# Cubesat.net
KiCad netlist of a schematic drawn in EAGLE
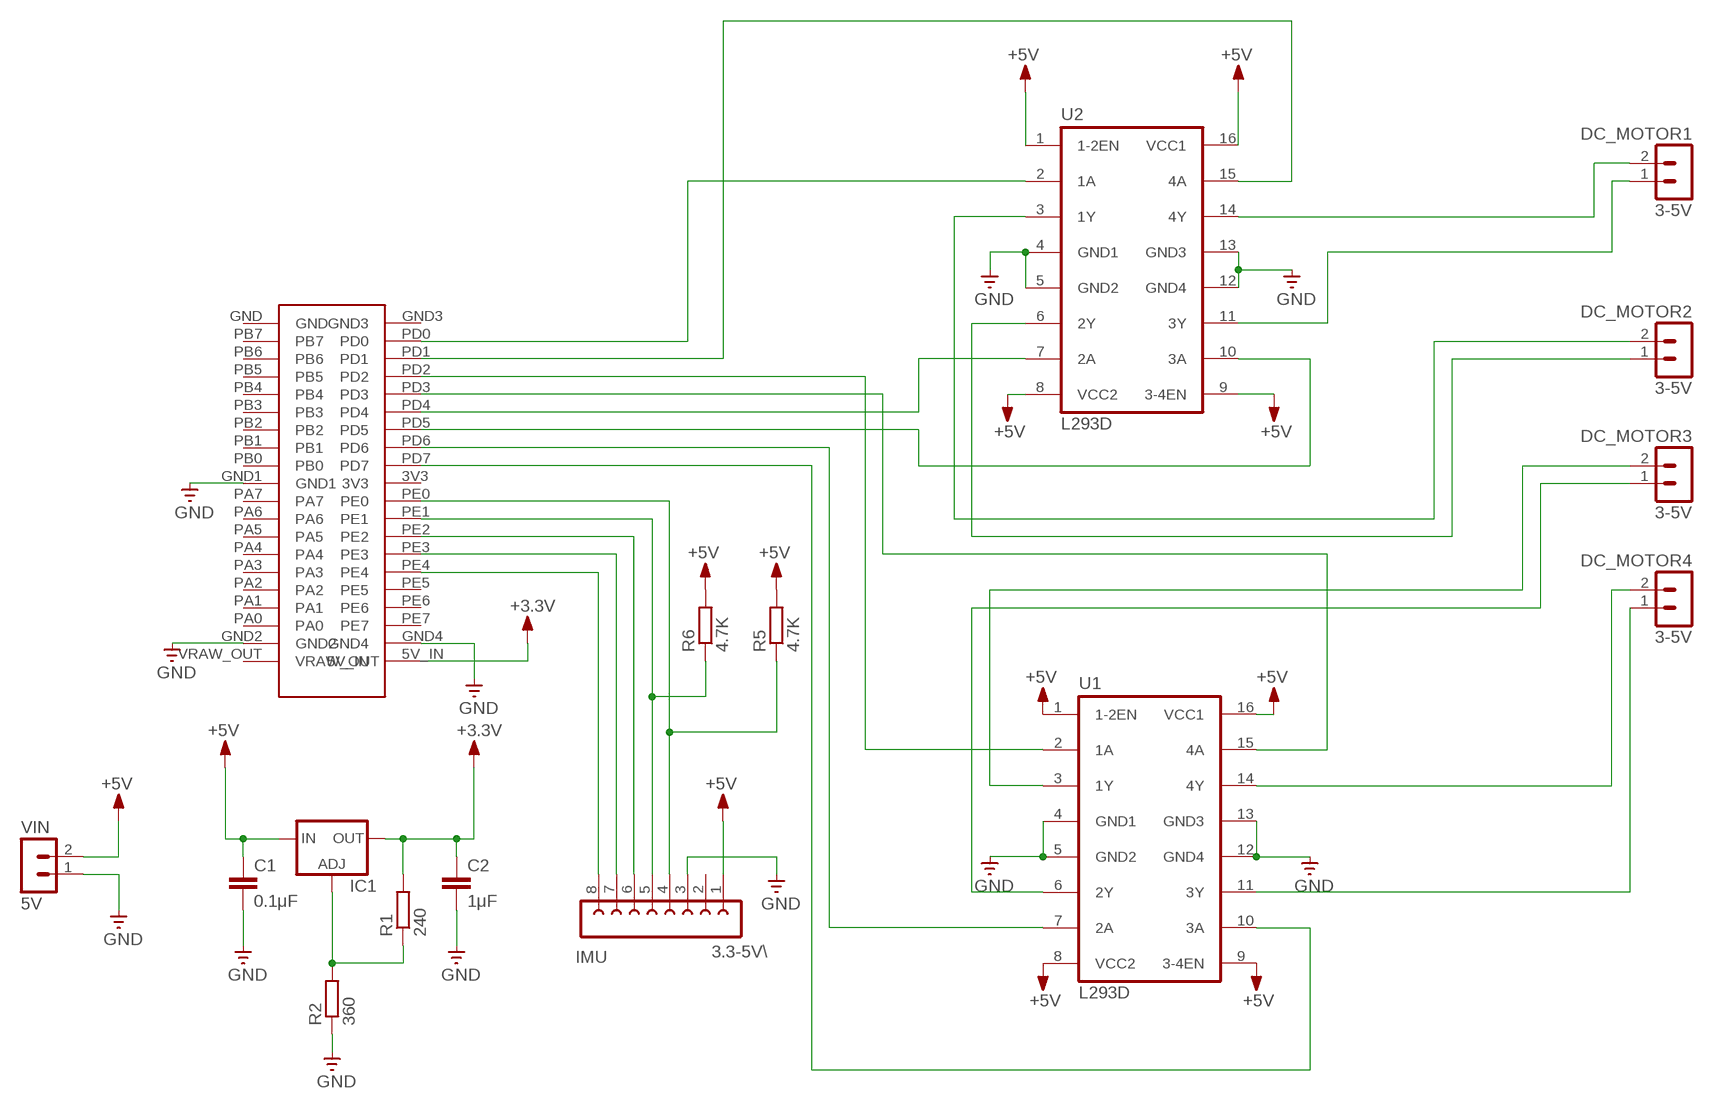
[diagram p0: schematic, sheet 1]

(export (version "E")
  (design (tool "Eeschema 10.0.6"))
  (components
    (comp (ref "C1")
      (value "0.1μF")
      (footprint "eagle-import:C1210")
      (libsource (lib "eagle-import") (part "C-EUC1210"))
    )
    (comp (ref "C2")
      (value "1μF")
      (footprint "eagle-import:C1210")
      (libsource (lib "eagle-import") (part "C-EUC1210"))
    )
    (comp (ref "DC_MOTOR1")
      (value "3-5V")
      (footprint "eagle-import:MA02-1Y")
      (libsource (lib "eagle-import") (part "MA02-1Y"))
    )
    (comp (ref "DC_MOTOR2")
      (value "3-5V")
      (footprint "eagle-import:MA02-1Y")
      (libsource (lib "eagle-import") (part "MA02-1Y"))
    )
    (comp (ref "DC_MOTOR3")
      (value "3-5V")
      (footprint "eagle-import:MA02-1Y")
      (libsource (lib "eagle-import") (part "MA02-1Y"))
    )
    (comp (ref "DC_MOTOR4")
      (value "3-5V")
      (footprint "eagle-import:MA02-1Y")
      (libsource (lib "eagle-import") (part "MA02-1Y"))
    )
    (comp (ref "IC1")
      (value "LM317TS")
      (footprint "eagle-import:317TS")
      (libsource (lib "eagle-import") (part "LM317TS"))
    )
    (comp (ref "IMU")
      (value "3.3-5V\\")
      (footprint "eagle-import:FE08-1")
      (libsource (lib "eagle-import") (part "FE08-1"))
    )
    (comp (ref "R1")
      (value "240")
      (footprint "eagle-import:M2012")
      (libsource (lib "eagle-import") (part "R-EU_M2012"))
    )
    (comp (ref "R2")
      (value "360")
      (footprint "eagle-import:M2012")
      (libsource (lib "eagle-import") (part "R-EU_M2012"))
    )
    (comp (ref "R5")
      (value "4.7K")
      (footprint "eagle-import:M2012")
      (libsource (lib "eagle-import") (part "R-EU_M2012"))
    )
    (comp (ref "R6")
      (value "4.7K")
      (footprint "eagle-import:M2012")
      (libsource (lib "eagle-import") (part "R-EU_M2012"))
    )
    (comp (ref "U1")
      (value "L293D")
      (footprint "eagle-import:DIL16")
      (libsource (lib "eagle-import") (part "L293D"))
    )
    (comp (ref "U2")
      (value "L293D")
      (footprint "eagle-import:DIL16")
      (libsource (lib "eagle-import") (part "L293D"))
    )
    (comp (ref "VIN")
      (value "5V")
      (footprint "eagle-import:MA02-1Y")
      (libsource (lib "eagle-import") (part "MA02-1Y"))
    )
    (comp (ref "XMEGA256A3U")
      (value "ATXMEGA256A3U")
      (footprint "eagle-import:ATXMEGA256A3U")
      (libsource (lib "eagle-import") (part "ATXMEGA256A3U"))
    )
  )
  (nets
    (net (code "1") (name "+3.3V") (class "Default")
      (node (ref "C1") (pin "1") (pinfunction "1_1") (pintype "passive"))
      (node (ref "C2") (pin "1") (pinfunction "1_1") (pintype "passive"))
      (node (ref "IC1") (pin "2") (pinfunction "OUT_2") (pintype "passive"))
      (node (ref "IC1") (pin "3") (pinfunction "IN_3") (pintype "input"))
      (node (ref "IMU") (pin "1") (pinfunction "1_1") (pintype "passive"))
      (node (ref "R1") (pin "2") (pinfunction "2_2") (pintype "passive"))
      (node (ref "R5") (pin "2") (pinfunction "2_2") (pintype "passive"))
      (node (ref "R6") (pin "2") (pinfunction "2_2") (pintype "passive"))
      (node (ref "U1") (pin "1") (pinfunction "1-2EN_1") (pintype "input"))
      (node (ref "U1") (pin "16") (pinfunction "VCC1_16") (pintype "power_in"))
      (node (ref "U1") (pin "8") (pinfunction "VCC2_8") (pintype "power_in"))
      (node (ref "U1") (pin "9") (pinfunction "3-4EN_9") (pintype "input"))
      (node (ref "U2") (pin "1") (pinfunction "1-2EN_1") (pintype "input"))
      (node (ref "U2") (pin "16") (pinfunction "VCC1_16") (pintype "power_in"))
      (node (ref "U2") (pin "8") (pinfunction "VCC2_8") (pintype "power_in"))
      (node (ref "U2") (pin "9") (pinfunction "3-4EN_9") (pintype "input"))
      (node (ref "VIN") (pin "2") (pinfunction "2_2") (pintype "passive"))
      (node (ref "XMEGA256A3U") (pin "5V_IN") (pinfunction "5V_IN_5V_IN") (pintype "bidirectional"))
    )
    (net (code "2") (name "GND") (class "Default")
      (node (ref "C1") (pin "2") (pinfunction "2_2") (pintype "passive"))
      (node (ref "C2") (pin "2") (pinfunction "2_2") (pintype "passive"))
      (node (ref "IMU") (pin "3") (pinfunction "3_3") (pintype "passive"))
      (node (ref "R2") (pin "1") (pinfunction "1_1") (pintype "passive"))
      (node (ref "U1") (pin "12") (pinfunction "GND4_12") (pintype "power_in"))
      (node (ref "U1") (pin "13") (pinfunction "GND3_13") (pintype "power_in"))
      (node (ref "U1") (pin "4") (pinfunction "GND1_4") (pintype "power_in"))
      (node (ref "U1") (pin "5") (pinfunction "GND2_5") (pintype "power_in"))
      (node (ref "U2") (pin "12") (pinfunction "GND4_12") (pintype "power_in"))
      (node (ref "U2") (pin "13") (pinfunction "GND3_13") (pintype "power_in"))
      (node (ref "U2") (pin "4") (pinfunction "GND1_4") (pintype "power_in"))
      (node (ref "U2") (pin "5") (pinfunction "GND2_5") (pintype "power_in"))
      (node (ref "VIN") (pin "1") (pinfunction "1_1") (pintype "passive"))
      (node (ref "XMEGA256A3U") (pin "GND1") (pinfunction "GND1_GND1") (pintype "bidirectional"))
      (node (ref "XMEGA256A3U") (pin "GND2") (pinfunction "GND2_GND2") (pintype "bidirectional"))
      (node (ref "XMEGA256A3U") (pin "GND4") (pinfunction "GND4_GND4") (pintype "bidirectional"))
    )
    (net (code "3") (name "Net-(IC1-ADJ)") (class "Default")
      (node (ref "IC1") (pin "1") (pinfunction "ADJ_1") (pintype "input"))
      (node (ref "R1") (pin "1") (pinfunction "1_1") (pintype "passive"))
      (node (ref "R2") (pin "2") (pinfunction "2_2") (pintype "passive"))
    )
    (net (code "4") (name "Net-(IMU-Pad4)") (class "Default")
      (node (ref "IMU") (pin "4") (pinfunction "4_4") (pintype "passive"))
      (node (ref "R5") (pin "1") (pinfunction "1_1") (pintype "passive"))
      (node (ref "XMEGA256A3U") (pin "PE0") (pinfunction "PE0_PE0") (pintype "bidirectional"))
    )
    (net (code "5") (name "Net-(IMU-Pad5)") (class "Default")
      (node (ref "IMU") (pin "5") (pinfunction "5_5") (pintype "passive"))
      (node (ref "R6") (pin "1") (pinfunction "1_1") (pintype "passive"))
      (node (ref "XMEGA256A3U") (pin "PE1") (pinfunction "PE1_PE1") (pintype "bidirectional"))
    )
    (net (code "6") (name "Net-(IMU-Pad6)") (class "Default")
      (node (ref "IMU") (pin "6") (pinfunction "6_6") (pintype "passive"))
      (node (ref "XMEGA256A3U") (pin "PE2") (pinfunction "PE2_PE2") (pintype "bidirectional"))
    )
    (net (code "7") (name "Net-(IMU-Pad7)") (class "Default")
      (node (ref "IMU") (pin "7") (pinfunction "7_7") (pintype "passive"))
      (node (ref "XMEGA256A3U") (pin "PE3") (pinfunction "PE3_PE3") (pintype "bidirectional"))
    )
    (net (code "8") (name "Net-(IMU-Pad8)") (class "Default")
      (node (ref "IMU") (pin "8") (pinfunction "8_8") (pintype "passive"))
      (node (ref "XMEGA256A3U") (pin "PE4") (pinfunction "PE4_PE4") (pintype "bidirectional"))
    )
    (net (code "9") (name "Net-(U1-1A)") (class "Default")
      (node (ref "U1") (pin "2") (pinfunction "1A_2") (pintype "input"))
      (node (ref "XMEGA256A3U") (pin "PD2") (pinfunction "PD2_PD2") (pintype "bidirectional"))
    )
    (net (code "10") (name "Net-(U1-1Y)") (class "Default")
      (node (ref "DC_MOTOR3") (pin "2") (pinfunction "2_2") (pintype "passive"))
      (node (ref "U1") (pin "3") (pinfunction "1Y_3") (pintype "output"))
    )
    (net (code "11") (name "Net-(U1-2A)") (class "Default")
      (node (ref "U1") (pin "7") (pinfunction "2A_7") (pintype "input"))
      (node (ref "XMEGA256A3U") (pin "PD6") (pinfunction "PD6_PD6") (pintype "bidirectional"))
    )
    (net (code "12") (name "Net-(U1-2Y)") (class "Default")
      (node (ref "DC_MOTOR3") (pin "1") (pinfunction "1_1") (pintype "passive"))
      (node (ref "U1") (pin "6") (pinfunction "2Y_6") (pintype "output"))
    )
    (net (code "13") (name "Net-(U1-3A)") (class "Default")
      (node (ref "U1") (pin "10") (pinfunction "3A_10") (pintype "input"))
      (node (ref "XMEGA256A3U") (pin "PD7") (pinfunction "PD7_PD7") (pintype "bidirectional"))
    )
    (net (code "14") (name "Net-(U1-3Y)") (class "Default")
      (node (ref "DC_MOTOR4") (pin "1") (pinfunction "1_1") (pintype "passive"))
      (node (ref "U1") (pin "11") (pinfunction "3Y_11") (pintype "output"))
    )
    (net (code "15") (name "Net-(U1-4A)") (class "Default")
      (node (ref "U1") (pin "15") (pinfunction "4A_15") (pintype "input"))
      (node (ref "XMEGA256A3U") (pin "PD3") (pinfunction "PD3_PD3") (pintype "bidirectional"))
    )
    (net (code "16") (name "Net-(U1-4Y)") (class "Default")
      (node (ref "DC_MOTOR4") (pin "2") (pinfunction "2_2") (pintype "passive"))
      (node (ref "U1") (pin "14") (pinfunction "4Y_14") (pintype "output"))
    )
    (net (code "17") (name "Net-(U2-1A)") (class "Default")
      (node (ref "U2") (pin "2") (pinfunction "1A_2") (pintype "input"))
      (node (ref "XMEGA256A3U") (pin "PD0") (pinfunction "PD0_PD0") (pintype "bidirectional"))
    )
    (net (code "18") (name "Net-(U2-1Y)") (class "Default")
      (node (ref "DC_MOTOR2") (pin "2") (pinfunction "2_2") (pintype "passive"))
      (node (ref "U2") (pin "3") (pinfunction "1Y_3") (pintype "output"))
    )
    (net (code "19") (name "Net-(U2-2A)") (class "Default")
      (node (ref "U2") (pin "7") (pinfunction "2A_7") (pintype "input"))
      (node (ref "XMEGA256A3U") (pin "PD4") (pinfunction "PD4_PD4") (pintype "bidirectional"))
    )
    (net (code "20") (name "Net-(U2-2Y)") (class "Default")
      (node (ref "DC_MOTOR2") (pin "1") (pinfunction "1_1") (pintype "passive"))
      (node (ref "U2") (pin "6") (pinfunction "2Y_6") (pintype "output"))
    )
    (net (code "21") (name "Net-(U2-3A)") (class "Default")
      (node (ref "U2") (pin "10") (pinfunction "3A_10") (pintype "input"))
      (node (ref "XMEGA256A3U") (pin "PD5") (pinfunction "PD5_PD5") (pintype "bidirectional"))
    )
    (net (code "22") (name "Net-(U2-3Y)") (class "Default")
      (node (ref "DC_MOTOR1") (pin "1") (pinfunction "1_1") (pintype "passive"))
      (node (ref "U2") (pin "11") (pinfunction "3Y_11") (pintype "output"))
    )
    (net (code "23") (name "Net-(U2-4A)") (class "Default")
      (node (ref "U2") (pin "15") (pinfunction "4A_15") (pintype "input"))
      (node (ref "XMEGA256A3U") (pin "PD1") (pinfunction "PD1_PD1") (pintype "bidirectional"))
    )
    (net (code "24") (name "Net-(U2-4Y)") (class "Default")
      (node (ref "DC_MOTOR1") (pin "2") (pinfunction "2_2") (pintype "passive"))
      (node (ref "U2") (pin "14") (pinfunction "4Y_14") (pintype "output"))
    )
    (net (code "25") (name "unconnected-(IMU-Pad2)") (class "Default")
      (node (ref "IMU") (pin "2") (pinfunction "2_2") (pintype "passive"))
    )
    (net (code "26") (name "unconnected-(XMEGA256A3U-Pad3V3)") (class "Default")
      (node (ref "XMEGA256A3U") (pin "3V3") (pinfunction "3V3_3V3") (pintype "bidirectional"))
    )
    (net (code "27") (name "unconnected-(XMEGA256A3U-PadGND)") (class "Default")
      (node (ref "XMEGA256A3U") (pin "GND") (pinfunction "GND_GND") (pintype "bidirectional"))
    )
    (net (code "28") (name "unconnected-(XMEGA256A3U-PadGND3)") (class "Default")
      (node (ref "XMEGA256A3U") (pin "GND3") (pinfunction "GND3_GND3") (pintype "bidirectional"))
    )
    (net (code "29") (name "unconnected-(XMEGA256A3U-PadPA0)") (class "Default")
      (node (ref "XMEGA256A3U") (pin "PA0") (pinfunction "PA0_PA0") (pintype "bidirectional"))
    )
    (net (code "30") (name "unconnected-(XMEGA256A3U-PadPA1)") (class "Default")
      (node (ref "XMEGA256A3U") (pin "PA1") (pinfunction "PA1_PA1") (pintype "bidirectional"))
    )
    (net (code "31") (name "unconnected-(XMEGA256A3U-PadPA2)") (class "Default")
      (node (ref "XMEGA256A3U") (pin "PA2") (pinfunction "PA2_PA2") (pintype "bidirectional"))
    )
    (net (code "32") (name "unconnected-(XMEGA256A3U-PadPA3)") (class "Default")
      (node (ref "XMEGA256A3U") (pin "PA3") (pinfunction "PA3_PA3") (pintype "bidirectional"))
    )
    (net (code "33") (name "unconnected-(XMEGA256A3U-PadPA4)") (class "Default")
      (node (ref "XMEGA256A3U") (pin "PA4") (pinfunction "PA4_PA4") (pintype "bidirectional"))
    )
    (net (code "34") (name "unconnected-(XMEGA256A3U-PadPA5)") (class "Default")
      (node (ref "XMEGA256A3U") (pin "PA5") (pinfunction "PA5_PA5") (pintype "bidirectional"))
    )
    (net (code "35") (name "unconnected-(XMEGA256A3U-PadPA6)") (class "Default")
      (node (ref "XMEGA256A3U") (pin "PA6") (pinfunction "PA6_PA6") (pintype "bidirectional"))
    )
    (net (code "36") (name "unconnected-(XMEGA256A3U-PadPA7)") (class "Default")
      (node (ref "XMEGA256A3U") (pin "PA7") (pinfunction "PA7_PA7") (pintype "bidirectional"))
    )
    (net (code "37") (name "unconnected-(XMEGA256A3U-PadPB0)") (class "Default")
      (node (ref "XMEGA256A3U") (pin "PB0") (pinfunction "PB0_PB0") (pintype "bidirectional"))
    )
    (net (code "38") (name "unconnected-(XMEGA256A3U-PadPB1)") (class "Default")
      (node (ref "XMEGA256A3U") (pin "PB1") (pinfunction "PB1_PB1") (pintype "bidirectional"))
    )
    (net (code "39") (name "unconnected-(XMEGA256A3U-PadPB2)") (class "Default")
      (node (ref "XMEGA256A3U") (pin "PB2") (pinfunction "PB2_PB2") (pintype "bidirectional"))
    )
    (net (code "40") (name "unconnected-(XMEGA256A3U-PadPB3)") (class "Default")
      (node (ref "XMEGA256A3U") (pin "PB3") (pinfunction "PB3_PB3") (pintype "bidirectional"))
    )
    (net (code "41") (name "unconnected-(XMEGA256A3U-PadPB4)") (class "Default")
      (node (ref "XMEGA256A3U") (pin "PB4") (pinfunction "PB4_PB4") (pintype "bidirectional"))
    )
    (net (code "42") (name "unconnected-(XMEGA256A3U-PadPB5)") (class "Default")
      (node (ref "XMEGA256A3U") (pin "PB5") (pinfunction "PB5_PB5") (pintype "bidirectional"))
    )
    (net (code "43") (name "unconnected-(XMEGA256A3U-PadPB6)") (class "Default")
      (node (ref "XMEGA256A3U") (pin "PB6") (pinfunction "PB6_PB6") (pintype "bidirectional"))
    )
    (net (code "44") (name "unconnected-(XMEGA256A3U-PadPB7)") (class "Default")
      (node (ref "XMEGA256A3U") (pin "PB7") (pinfunction "PB7_PB7") (pintype "bidirectional"))
    )
    (net (code "45") (name "unconnected-(XMEGA256A3U-PadPE5)") (class "Default")
      (node (ref "XMEGA256A3U") (pin "PE5") (pinfunction "PE5_PE5") (pintype "bidirectional"))
    )
    (net (code "46") (name "unconnected-(XMEGA256A3U-PadPE6)") (class "Default")
      (node (ref "XMEGA256A3U") (pin "PE6") (pinfunction "PE6_PE6") (pintype "bidirectional"))
    )
    (net (code "47") (name "unconnected-(XMEGA256A3U-PadPE7)") (class "Default")
      (node (ref "XMEGA256A3U") (pin "PE7") (pinfunction "PE7_PE7") (pintype "bidirectional"))
    )
    (net (code "48") (name "unconnected-(XMEGA256A3U-PadVRAW_OUT)") (class "Default")
      (node (ref "XMEGA256A3U") (pin "VRAW_OUT") (pinfunction "VRAW_OUT_VRAW_OUT") (pintype "bidirectional"))
    )
  )
)
